# schematic.net
KiCad netlist of a schematic drawn in EAGLE
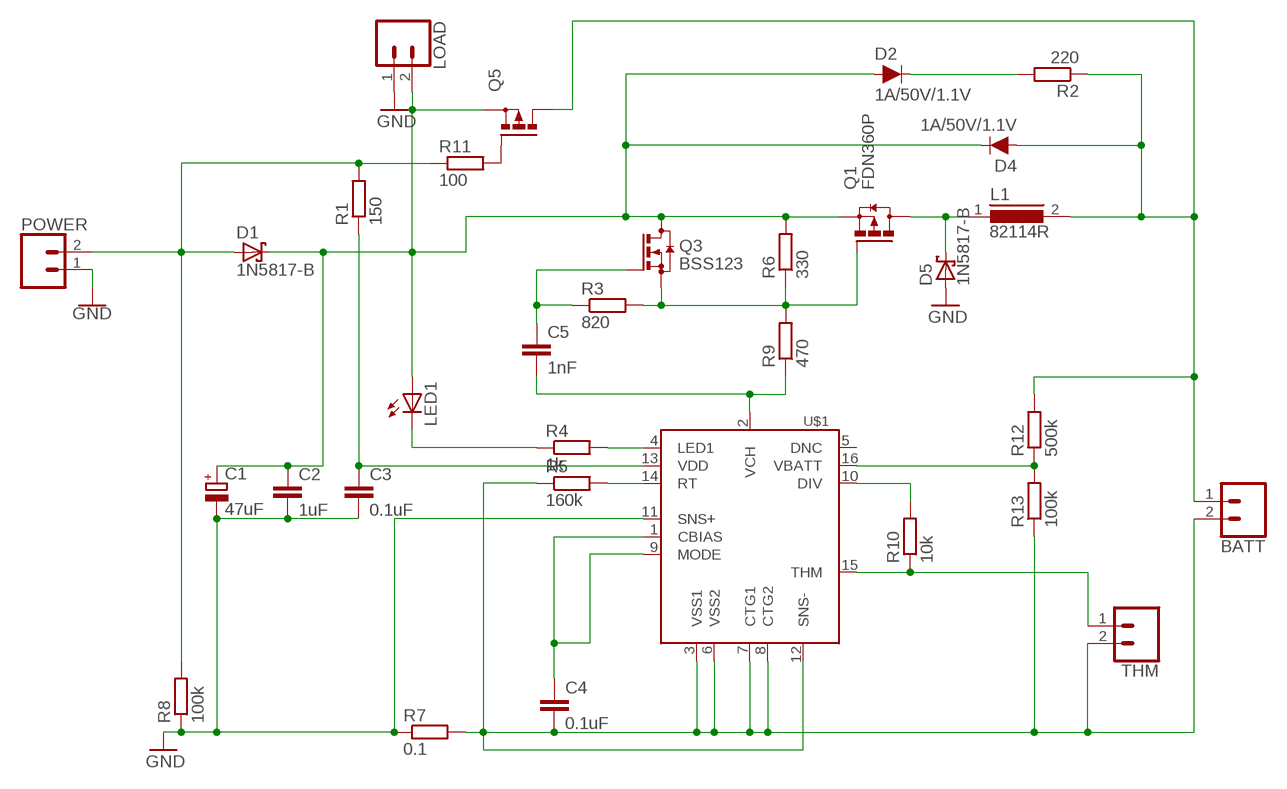
[diagram p0: schematic, sheet 1]

(export (version "E")
  (design (tool "Eeschema 10.0.6"))
  (components
    (comp (ref "BATT")
      (value "CONN_02POLAR")
      (footprint "eagle-import:MOLEX-1X2")
      (libsource (lib "eagle-import") (part "CONN_02POLAR"))
    )
    (comp (ref "C1")
      (value "47uF")
      (footprint "eagle-import:E2,5-6")
      (libsource (lib "eagle-import") (part "CPOL-EUE2.5-6"))
    )
    (comp (ref "C2")
      (value "1uF")
      (footprint "eagle-import:C025-025X050")
      (libsource (lib "eagle-import") (part "C-EU025-025X050"))
    )
    (comp (ref "C3")
      (value "0.1uF")
      (footprint "eagle-import:C025-025X050")
      (libsource (lib "eagle-import") (part "C-EU025-025X050"))
    )
    (comp (ref "C4")
      (value "0.1uF")
      (footprint "eagle-import:C025-025X050")
      (libsource (lib "eagle-import") (part "C-EU025-025X050"))
    )
    (comp (ref "C5")
      (value "1nF")
      (footprint "eagle-import:C025-025X050")
      (libsource (lib "eagle-import") (part "C-EU025-025X050"))
    )
    (comp (ref "D1")
      (value "1N5817-B")
      (footprint "eagle-import:DO41-7.6")
      (libsource (lib "eagle-import") (part "1N5817-B"))
    )
    (comp (ref "D2")
      (value "1A/50V/1.1V")
      (footprint "eagle-import:DIODE-1N4001")
      (libsource (lib "eagle-import") (part "DIODE-PTH"))
    )
    (comp (ref "D4")
      (value "1A/50V/1.1V")
      (footprint "eagle-import:DIODE-1N4001")
      (libsource (lib "eagle-import") (part "DIODE-PTH"))
    )
    (comp (ref "D5")
      (value "1N5817-B")
      (footprint "eagle-import:DO41-7.6")
      (libsource (lib "eagle-import") (part "1N5817-B"))
    )
    (comp (ref "L1")
      (value "82114R")
      (footprint "eagle-import:82114R")
      (libsource (lib "eagle-import") (part "82114R"))
    )
    (comp (ref "LED1")
      (value "LED5MM")
      (footprint "eagle-import:LED5MM")
      (libsource (lib "eagle-import") (part "LED5MM"))
    )
    (comp (ref "LOAD")
      (value "CONN_02POLAR")
      (footprint "eagle-import:MOLEX-1X2")
      (libsource (lib "eagle-import") (part "CONN_02POLAR"))
    )
    (comp (ref "POWER")
      (value "CONN_02POLAR")
      (footprint "eagle-import:MOLEX-1X2")
      (libsource (lib "eagle-import") (part "CONN_02POLAR"))
    )
    (comp (ref "Q1")
      (value "FDN360P")
      (footprint "eagle-import:SUPER-SOT3")
      (libsource (lib "eagle-import") (part "FDN360P"))
    )
    (comp (ref "Q3")
      (value "BSS123")
      (footprint "eagle-import:SOT23")
      (libsource (lib "eagle-import") (part "BSS123"))
    )
    (comp (ref "Q5")
      (value "PMOSFET_PTO220BV")
      (footprint "eagle-import:TO220BV")
      (libsource (lib "eagle-import") (part "PMOSFET_PTO220BV"))
    )
    (comp (ref "R1")
      (value "150")
      (footprint "eagle-import:0207_10")
      (libsource (lib "eagle-import") (part "R-EU_0207/10"))
    )
    (comp (ref "R2")
      (value "220")
      (footprint "eagle-import:0207_10")
      (libsource (lib "eagle-import") (part "R-EU_0207/10"))
    )
    (comp (ref "R3")
      (value "820")
      (footprint "eagle-import:0207_10")
      (libsource (lib "eagle-import") (part "R-EU_0207/10"))
    )
    (comp (ref "R4")
      (value "1k")
      (footprint "eagle-import:0207_10")
      (libsource (lib "eagle-import") (part "R-EU_0207/10"))
    )
    (comp (ref "R5")
      (value "160k")
      (footprint "eagle-import:0207_10")
      (libsource (lib "eagle-import") (part "R-EU_0207/10"))
    )
    (comp (ref "R6")
      (value "330")
      (footprint "eagle-import:0207_10")
      (libsource (lib "eagle-import") (part "R-EU_0207/10"))
    )
    (comp (ref "R7")
      (value "0.1")
      (footprint "eagle-import:0207_10")
      (libsource (lib "eagle-import") (part "R-EU_0207/10"))
    )
    (comp (ref "R8")
      (value "100k")
      (footprint "eagle-import:0207_10")
      (libsource (lib "eagle-import") (part "R-EU_0207/10"))
    )
    (comp (ref "R9")
      (value "470")
      (footprint "eagle-import:0207_10")
      (libsource (lib "eagle-import") (part "R-EU_0207/10"))
    )
    (comp (ref "R10")
      (value "10k")
      (footprint "eagle-import:0207_10")
      (libsource (lib "eagle-import") (part "R-EU_0207/10"))
    )
    (comp (ref "R11")
      (value "100")
      (footprint "eagle-import:0207_10")
      (libsource (lib "eagle-import") (part "R-EU_0207/10"))
    )
    (comp (ref "R12")
      (value "500k")
      (footprint "eagle-import:0207_10")
      (libsource (lib "eagle-import") (part "R-EU_0207/10"))
    )
    (comp (ref "R13")
      (value "100k")
      (footprint "eagle-import:0207_10")
      (libsource (lib "eagle-import") (part "R-EU_0207/10"))
    )
    (comp (ref "THM")
      (value "CONN_02")
      (footprint "eagle-import:1X02")
      (libsource (lib "eagle-import") (part "CONN_02"))
    )
    (comp (ref "U$1")
      (value "DS2715")
      (footprint "eagle-import:DS2715-SO16")
      (libsource (lib "eagle-import") (part "DS2715"))
    )
  )
  (nets
    (net (code "1") (name "GND") (class "Default")
      (node (ref "C1") (pin "-") (pinfunction "-_-") (pintype "passive"))
      (node (ref "C2") (pin "2") (pinfunction "2_2") (pintype "passive"))
      (node (ref "C3") (pin "2") (pinfunction "2_2") (pintype "passive"))
      (node (ref "D5") (pin "A") (pinfunction "A_A") (pintype "passive"))
      (node (ref "LOAD") (pin "1") (pinfunction "1_1") (pintype "passive"))
      (node (ref "POWER") (pin "1") (pinfunction "1_1") (pintype "passive"))
      (node (ref "R7") (pin "1") (pinfunction "1_1") (pintype "passive"))
      (node (ref "R8") (pin "1") (pinfunction "1_1") (pintype "passive"))
      (node (ref "U$1") (pin "11") (pinfunction "SNS+_11") (pintype "bidirectional"))
    )
    (net (code "2") (name "Net-(BATT-Pad1)") (class "Default")
      (node (ref "BATT") (pin "1") (pinfunction "1_1") (pintype "passive"))
      (node (ref "D4") (pin "A") (pinfunction "A_A") (pintype "passive"))
      (node (ref "L1") (pin "2") (pinfunction "2_2") (pintype "passive"))
      (node (ref "Q5") (pin "D") (pinfunction "D_D") (pintype "passive"))
      (node (ref "R12") (pin "2") (pinfunction "2_2") (pintype "passive"))
      (node (ref "R2") (pin "1") (pinfunction "1_1") (pintype "passive"))
    )
    (net (code "3") (name "Net-(D1-PadA)") (class "Default")
      (node (ref "D1") (pin "A") (pinfunction "A_A") (pintype "passive"))
      (node (ref "POWER") (pin "2") (pinfunction "2_2") (pintype "passive"))
      (node (ref "R1") (pin "2") (pinfunction "2_2") (pintype "passive"))
      (node (ref "R11") (pin "1") (pinfunction "1_1") (pintype "passive"))
      (node (ref "R8") (pin "2") (pinfunction "2_2") (pintype "passive"))
    )
    (net (code "4") (name "Net-(D2-PadC)") (class "Default")
      (node (ref "D2") (pin "C") (pinfunction "C_C") (pintype "passive"))
      (node (ref "R2") (pin "2") (pinfunction "2_2") (pintype "passive"))
    )
    (net (code "5") (name "Net-(LED1-C)") (class "Default")
      (node (ref "LED1") (pin "K") (pinfunction "C_K") (pintype "passive"))
      (node (ref "R4") (pin "1") (pinfunction "1_1") (pintype "passive"))
    )
    (net (code "6") (name "Net-(Q1-D)") (class "Default")
      (node (ref "D5") (pin "C") (pinfunction "C_C") (pintype "passive"))
      (node (ref "L1") (pin "1") (pinfunction "1_1") (pintype "passive"))
      (node (ref "Q1") (pin "3") (pinfunction "D_3") (pintype "passive"))
    )
    (net (code "7") (name "Net-(Q1-G)") (class "Default")
      (node (ref "Q1") (pin "1") (pinfunction "G_1") (pintype "passive"))
      (node (ref "Q3") (pin "2") (pinfunction "S_2") (pintype "passive"))
      (node (ref "R3") (pin "2") (pinfunction "2_2") (pintype "passive"))
      (node (ref "R6") (pin "1") (pinfunction "1_1") (pintype "passive"))
      (node (ref "R9") (pin "2") (pinfunction "2_2") (pintype "passive"))
    )
    (net (code "8") (name "Net-(Q1-S)") (class "Default")
      (node (ref "C1") (pin "+") (pinfunction "+_+") (pintype "passive"))
      (node (ref "C2") (pin "1") (pinfunction "1_1") (pintype "passive"))
      (node (ref "D1") (pin "C") (pinfunction "C_C") (pintype "passive"))
      (node (ref "D2") (pin "A") (pinfunction "A_A") (pintype "passive"))
      (node (ref "D4") (pin "C") (pinfunction "C_C") (pintype "passive"))
      (node (ref "LED1") (pin "A") (pinfunction "A_A") (pintype "passive"))
      (node (ref "LOAD") (pin "2") (pinfunction "2_2") (pintype "passive"))
      (node (ref "Q1") (pin "2") (pinfunction "S_2") (pintype "passive"))
      (node (ref "Q3") (pin "3") (pinfunction "D_3") (pintype "passive"))
      (node (ref "Q5") (pin "S") (pinfunction "S_S") (pintype "passive"))
      (node (ref "R6") (pin "2") (pinfunction "2_2") (pintype "passive"))
    )
    (net (code "9") (name "Net-(Q3-G)") (class "Default")
      (node (ref "C5") (pin "1") (pinfunction "1_1") (pintype "passive"))
      (node (ref "Q3") (pin "1") (pinfunction "G_1") (pintype "passive"))
      (node (ref "R3") (pin "1") (pinfunction "1_1") (pintype "passive"))
    )
    (net (code "10") (name "Net-(Q5-PadG)") (class "Default")
      (node (ref "Q5") (pin "G") (pinfunction "G_G") (pintype "passive"))
      (node (ref "R11") (pin "2") (pinfunction "2_2") (pintype "passive"))
    )
    (net (code "11") (name "Net-(U$1-CBIAS)") (class "Default")
      (node (ref "C4") (pin "1") (pinfunction "1_1") (pintype "passive"))
      (node (ref "U$1") (pin "1") (pinfunction "CBIAS_1") (pintype "bidirectional"))
      (node (ref "U$1") (pin "9") (pinfunction "MODE_9") (pintype "bidirectional"))
    )
    (net (code "12") (name "Net-(U$1-CTG1)") (class "Default")
      (node (ref "BATT") (pin "2") (pinfunction "2_2") (pintype "passive"))
      (node (ref "C4") (pin "2") (pinfunction "2_2") (pintype "passive"))
      (node (ref "R13") (pin "1") (pinfunction "1_1") (pintype "passive"))
      (node (ref "R5") (pin "1") (pinfunction "1_1") (pintype "passive"))
      (node (ref "R7") (pin "2") (pinfunction "2_2") (pintype "passive"))
      (node (ref "THM") (pin "2") (pinfunction "2_2") (pintype "passive"))
      (node (ref "U$1") (pin "12") (pinfunction "SNS-_12") (pintype "bidirectional"))
      (node (ref "U$1") (pin "3") (pinfunction "VSS1_3") (pintype "bidirectional"))
      (node (ref "U$1") (pin "6") (pinfunction "VSS2_6") (pintype "bidirectional"))
      (node (ref "U$1") (pin "7") (pinfunction "CTG1_7") (pintype "bidirectional"))
      (node (ref "U$1") (pin "8") (pinfunction "CTG2_8") (pintype "bidirectional"))
    )
    (net (code "13") (name "Net-(U$1-DIV)") (class "Default")
      (node (ref "R10") (pin "2") (pinfunction "2_2") (pintype "passive"))
      (node (ref "U$1") (pin "10") (pinfunction "DIV_10") (pintype "bidirectional"))
    )
    (net (code "14") (name "Net-(U$1-LED1)") (class "Default")
      (node (ref "R4") (pin "2") (pinfunction "2_2") (pintype "passive"))
      (node (ref "U$1") (pin "4") (pinfunction "LED1_4") (pintype "bidirectional"))
    )
    (net (code "15") (name "Net-(U$1-RT)") (class "Default")
      (node (ref "R5") (pin "2") (pinfunction "2_2") (pintype "passive"))
      (node (ref "U$1") (pin "14") (pinfunction "RT_14") (pintype "bidirectional"))
    )
    (net (code "16") (name "Net-(U$1-THM)") (class "Default")
      (node (ref "R10") (pin "1") (pinfunction "1_1") (pintype "passive"))
      (node (ref "THM") (pin "1") (pinfunction "1_1") (pintype "passive"))
      (node (ref "U$1") (pin "15") (pinfunction "THM_15") (pintype "bidirectional"))
    )
    (net (code "17") (name "Net-(U$1-VBATT)") (class "Default")
      (node (ref "R12") (pin "1") (pinfunction "1_1") (pintype "passive"))
      (node (ref "R13") (pin "2") (pinfunction "2_2") (pintype "passive"))
      (node (ref "U$1") (pin "16") (pinfunction "VBATT_16") (pintype "bidirectional"))
    )
    (net (code "18") (name "Net-(U$1-VCH)") (class "Default")
      (node (ref "C5") (pin "2") (pinfunction "2_2") (pintype "passive"))
      (node (ref "R9") (pin "1") (pinfunction "1_1") (pintype "passive"))
      (node (ref "U$1") (pin "2") (pinfunction "VCH_2") (pintype "bidirectional"))
    )
    (net (code "19") (name "Net-(U$1-VDD)") (class "Default")
      (node (ref "C3") (pin "1") (pinfunction "1_1") (pintype "passive"))
      (node (ref "R1") (pin "1") (pinfunction "1_1") (pintype "passive"))
      (node (ref "U$1") (pin "13") (pinfunction "VDD_13") (pintype "bidirectional"))
    )
    (net (code "20") (name "unconnected-(U$1-DNC-Pad5)") (class "Default")
      (node (ref "U$1") (pin "5") (pinfunction "DNC_5") (pintype "bidirectional"))
    )
  )
)
